# Elevador.net
KiCad netlist of a schematic drawn in Altium Designer
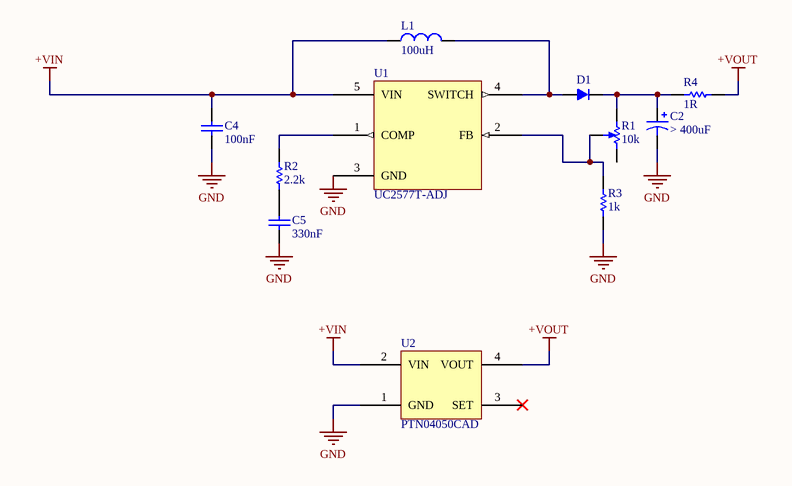
[diagram p0: Elevador.SchDoc]

(export (version "E")
  (design (tool "Eeschema 10.0.6"))
  (components
    (comp (ref "C2")
      (value "> 400uF")
      (footprint "CDRLib_PCB:C 12.5 x 25")
      (description "Capacitor polarizado.")
      (fields (field (name ".CREATOR") "SR"))
      (libsource (lib "CDRLib_SCH") (part "C POL"))
    )
    (comp (ref "C4")
      (value "100nF")
      (footprint "CDRLib_PCB:C 1206")
      (description "Capacitor")
      (fields (field (name ".CREATOR") "SR"))
      (libsource (lib "CDRLib_SCH") (part "C"))
    )
    (comp (ref "C5")
      (value "330nF")
      (footprint "CDRLib_PCB:C Lenteja")
      (description "Capacitor")
      (fields (field (name ".CREATOR") "SR"))
      (libsource (lib "CDRLib_SCH") (part "C"))
    )
    (comp (ref "D1")
      (value "DIODO")
      (footprint "D 3528")
      (fields (field (name ".CREATOR") "SR") (field (name ".PCBCHECK") "SR") (field (name ".SCHCHECK") "SR"))
      (libsource (lib "CDRLib_SCH") (part "DIODO"))
    )
    (comp (ref "L1")
      (value "100uH")
      (footprint "CDRLib_PCB:L SW TH")
      (description "Inductor")
      (libsource (lib "CDRLib_SCH") (part "L"))
    )
    (comp (ref "R1")
      (value "10k")
      (footprint "BOURNS-3596W")
      (description "TRIMMER 5K OHM 0.5W PC PIN")
      (fields
        (field (name "MANUFACTURER") "Bourns Inc.")
        (field (name "MANUFACTURER PART NUMBER") "3296W-1-502")
        (field (name ".CREATOR") "SR")
        (field (name ".PCBCHECK") "SR")
        (field (name ".SCHCHECK") "SR")
      )
      (libsource (lib "CDRLib_SCH") (part "3296W-1-502"))
    )
    (comp (ref "R2")
      (value "2.2k")
      (footprint "CDRLib_PCB:R THRU")
      (description "Resistencia")
      (fields (field (name ".CREATOR") "SR"))
      (libsource (lib "CDRLib_SCH") (part "R"))
    )
    (comp (ref "R3")
      (value "1k")
      (footprint "CDRLib_PCB:R THRU")
      (description "Resistencia")
      (fields (field (name ".CREATOR") "SR"))
      (libsource (lib "CDRLib_SCH") (part "R"))
    )
    (comp (ref "R4")
      (value "1R")
      (footprint "CDRLib_PCB:R 0805")
      (description "Resistencia")
      (fields (field (name ".CREATOR") "SR"))
      (libsource (lib "CDRLib_SCH") (part "R"))
    )
    (comp (ref "U1")
      (value "UC2577T-ADJ")
      (footprint "CDRLib_PCB:TO220 5")
      (description "IC REG MULTI CONFIG ADJ 3A TO220")
      (fields
        (field (name "MANUFACTURER") "Texas Instruments")
        (field (name ".CREATOR") "SR")
        (field (name ".PCBCHECK") "SR")
        (field (name ".SCHCHECK") "SR")
      )
      (libsource (lib "CDRLib_SCH") (part "UC2577T-ADJ"))
    )
    (comp (ref "U2")
      (value "PTN04050CAD")
      (footprint "CDRLib_PCB:PTN04050")
      (description "REG SW 5-15V 2.4A HORZ T/H")
      (fields
        (field (name "MANUFACTURER") "Texas Instruments")
        (field (name ".CREATOR") "SR")
        (field (name ".PCBCHECK") "SR")
        (field (name ".SCHCHECK") "SR")
      )
      (libsource (lib "CDRLib_SCH") (part "PTN04050CAD"))
    )
  )
  (nets
    (net (code "1") (name "+VIN") (class "Default")
      (node (ref "C4") (pin "2") (pinfunction "2_2") (pintype "passive"))
      (node (ref "L1") (pin "1") (pinfunction "1_1") (pintype "passive"))
      (node (ref "U1") (pin "5") (pinfunction "VIN_5") (pintype "power_in"))
      (node (ref "U2") (pin "2") (pinfunction "VIN_2") (pintype "passive"))
    )
    (net (code "2") (name "+VOUT") (class "Default")
      (node (ref "R4") (pin "2") (pinfunction "2_2") (pintype "passive"))
      (node (ref "U2") (pin "4") (pinfunction "VOUT_4") (pintype "passive"))
    )
    (net (code "3") (name "GND") (class "Default")
      (node (ref "C2") (pin "2") (pinfunction "2_2") (pintype "passive"))
      (node (ref "C4") (pin "1") (pinfunction "1_1") (pintype "passive"))
      (node (ref "C5") (pin "1") (pinfunction "1_1") (pintype "passive"))
      (node (ref "R3") (pin "1") (pinfunction "1_1") (pintype "passive"))
      (node (ref "U1") (pin "3") (pinfunction "GND_3") (pintype "power_in"))
      (node (ref "U2") (pin "1") (pinfunction "GND_1") (pintype "passive"))
    )
    (net (code "4") (name "Net-(C5-Pad2)") (class "Default")
      (node (ref "C5") (pin "2") (pinfunction "2_2") (pintype "passive"))
      (node (ref "R2") (pin "1") (pinfunction "1_1") (pintype "passive"))
    )
    (net (code "5") (name "Net-(D1-A)") (class "Default")
      (node (ref "D1") (pin "1") (pinfunction "A_1") (pintype "passive"))
      (node (ref "L1") (pin "2") (pinfunction "2_2") (pintype "passive"))
      (node (ref "U1") (pin "4") (pinfunction "SWITCH_4") (pintype "output"))
    )
    (net (code "6") (name "Net-(D1-K)") (class "Default")
      (node (ref "C2") (pin "1") (pinfunction "1_1") (pintype "passive"))
      (node (ref "D1") (pin "2") (pinfunction "K_2") (pintype "passive"))
      (node (ref "R1") (pin "1") (pinfunction "CCW_1") (pintype "passive"))
      (node (ref "R4") (pin "1") (pinfunction "1_1") (pintype "passive"))
    )
    (net (code "7") (name "Net-(R1-W)") (class "Default")
      (node (ref "R1") (pin "2") (pinfunction "W_2") (pintype "passive"))
      (node (ref "R3") (pin "2") (pinfunction "2_2") (pintype "passive"))
      (node (ref "U1") (pin "2") (pinfunction "FB_2") (pintype "input"))
    )
    (net (code "8") (name "Net-(U1-COMP)") (class "Default")
      (node (ref "R2") (pin "2") (pinfunction "2_2") (pintype "passive"))
      (node (ref "U1") (pin "1") (pinfunction "COMP_1") (pintype "output"))
    )
    (net (code "9") (name "unconnected-(R1-CW-Pad3)") (class "Default")
      (node (ref "R1") (pin "3") (pinfunction "CW_3") (pintype "passive"))
    )
    (net (code "10") (name "unconnected-(U2-SET-Pad3)") (class "Default")
      (node (ref "U2") (pin "3") (pinfunction "SET_3") (pintype "passive+no_connect"))
    )
  )
)
